# TCA785-W.net
KiCad netlist of a schematic drawn in Altium Designer
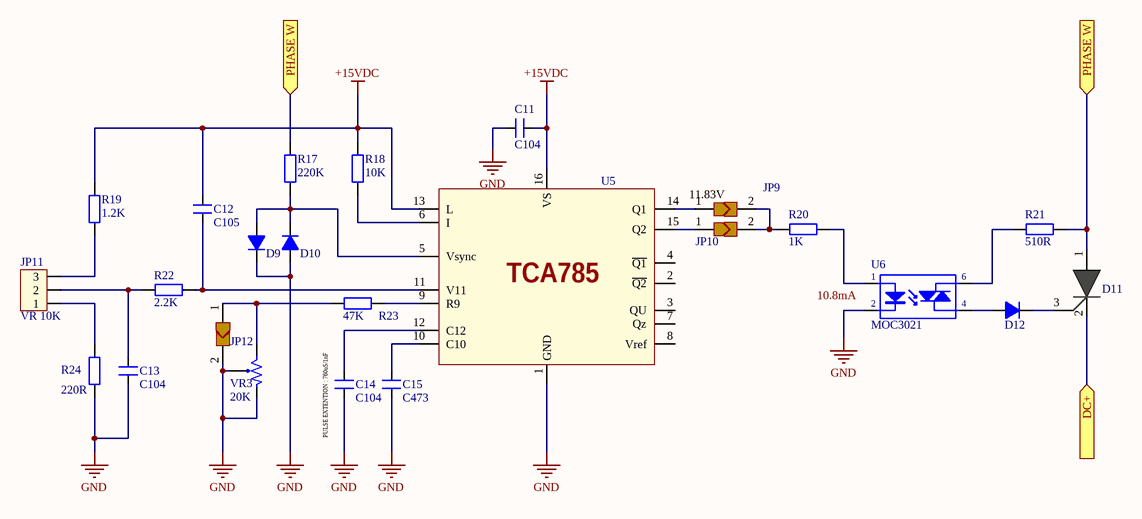
[diagram p0: TCA785-W.SchDoc]

(export (version "E")
  (design (tool "Eeschema 10.0.6"))
  (components
    (comp (ref "C11")
      (value "C104")
      (footprint "CN2-O")
      (description "CAP-gom")
      (libsource (lib "Sang_Library") (part "CAP-gom"))
    )
    (comp (ref "C12")
      (value "C105")
      (footprint "CN2-O")
      (description "CAP-gom")
      (libsource (lib "Sang_Library") (part "CAP-gom"))
    )
    (comp (ref "C13")
      (value "C104")
      (footprint "CN2-O")
      (description "CAP-gom")
      (libsource (lib "Sang_Library") (part "CAP-gom"))
    )
    (comp (ref "C14")
      (value "C104")
      (footprint "CN2-O")
      (description "CAP-gom")
      (libsource (lib "Sang_Library") (part "CAP-gom"))
    )
    (comp (ref "C15")
      (value "C473")
      (footprint "CN2-O")
      (description "CAP-gom")
      (libsource (lib "Sang_Library") (part "CAP-gom"))
    )
    (comp (ref "D9")
      (value "Diode  1N4007")
      (footprint "DO41-1A")
      (description "Diode 1A")
      (libsource (lib "Sang_Library") (part "Diode  1N4007"))
    )
    (comp (ref "D10")
      (value "Diode  1N4007")
      (footprint "DO41-1A")
      (description "Diode 1A")
      (libsource (lib "Sang_Library") (part "Diode  1N4007"))
    )
    (comp (ref "D11") (value "SCR") (footprint "TO-220") (libsource (lib "Huan") (part "BT151")))
    (comp (ref "D12")
      (value "Diode  1N4007")
      (footprint "DO41-1A")
      (description "Diode 1A")
      (libsource (lib "Sang_Library") (part "Diode  1N4007"))
    )
    (comp (ref "JP9")
      (value "PAD_Sellect")
      (footprint "PAD Select")
      (libsource (lib "Huan") (part "PAD_Sellect"))
    )
    (comp (ref "JP10")
      (value "PAD_Sellect")
      (footprint "PAD Select")
      (libsource (lib "Huan") (part "PAD_Sellect"))
    )
    (comp (ref "JP11")
      (value "VR 10K")
      (footprint "CON3")
      (description "Connector 3")
      (libsource (lib "syhaunguyen") (part "Con3"))
    )
    (comp (ref "JP12")
      (value "PAD_Sellect")
      (footprint "PAD Select")
      (libsource (lib "Huan") (part "PAD_Sellect"))
    )
    (comp (ref "R17")
      (value "220K")
      (footprint "R1/4W")
      (description "Resistor 1/4W")
      (libsource (lib "Sang_Library") (part "R1/4W"))
    )
    (comp (ref "R18")
      (value "10K")
      (footprint "R1/4W")
      (description "Resistor 1/4W")
      (libsource (lib "Sang_Library") (part "R1/4W"))
    )
    (comp (ref "R19")
      (value "1.2K")
      (footprint "R1/4W")
      (description "Resistor 1/4W")
      (libsource (lib "Sang_Library") (part "R1/4W"))
    )
    (comp (ref "R20")
      (value "1K")
      (footprint "R1/4W")
      (description "Resistor 1/4W")
      (libsource (lib "Sang_Library") (part "R1/4W"))
    )
    (comp (ref "R21")
      (value "510R")
      (footprint "R1/4W")
      (description "Resistor 1/4W")
      (libsource (lib "Sang_Library") (part "R1/4W"))
    )
    (comp (ref "R22")
      (value "2.2K")
      (footprint "R1/4W")
      (description "Resistor 1/4W")
      (libsource (lib "Sang_Library") (part "R1/4W"))
    )
    (comp (ref "R23")
      (value "47K")
      (footprint "R1/4W")
      (description "Resistor 1/4W")
      (libsource (lib "Sang_Library") (part "R1/4W"))
    )
    (comp (ref "R24")
      (value "220R")
      (footprint "R1/4W")
      (description "Resistor 1/4W")
      (libsource (lib "Sang_Library") (part "R1/4W"))
    )
    (comp (ref "U5") (value "TCA785Q") (footprint "DIP-16") (libsource (lib "Huan") (part "TCA785Q")))
    (comp (ref "U6")
      (value "MOC3021")
      (footprint "DIP6/W0.3 - MOC3021")
      (description "Single Opto")
      (libsource (lib "Sang_Library") (part "MOC3021"))
    )
    (comp (ref "VR3")
      (value "20K")
      (footprint "VR")
      (description "Var Resistor RM065")
      (libsource (lib "Sang_Library") (part "VR"))
    )
  )
  (nets
    (net (code "1") (name "+15VDC") (class "Default")
      (node (ref "C11") (pin "2") (pinfunction "2_2") (pintype "passive"))
      (node (ref "C12") (pin "2") (pinfunction "2_2") (pintype "passive"))
      (node (ref "R18") (pin "1") (pinfunction "1_1") (pintype "passive"))
      (node (ref "R19") (pin "2") (pinfunction "2_2") (pintype "passive"))
      (node (ref "U5") (pin "13") (pinfunction "L_13") (pintype "passive"))
      (node (ref "U5") (pin "16") (pinfunction "VS_16") (pintype "passive"))
    )
    (net (code "3") (name "/DC+") (class "Default")
      (node (ref "D11") (pin "2") (pinfunction "K_2") (pintype "passive"))
    )
    (net (code "4") (name "/PHASE W") (class "Default")
      (node (ref "D11") (pin "1") (pinfunction "A_1") (pintype "passive"))
      (node (ref "R17") (pin "1") (pinfunction "1_1") (pintype "passive"))
      (node (ref "R21") (pin "1") (pinfunction "1_1") (pintype "passive"))
    )
    (net (code "5") (name "GND") (class "Default")
      (node (ref "C11") (pin "1") (pinfunction "1_1") (pintype "passive"))
      (node (ref "C13") (pin "1") (pinfunction "1_1") (pintype "passive"))
      (node (ref "C14") (pin "1") (pinfunction "1_1") (pintype "passive"))
      (node (ref "C15") (pin "1") (pinfunction "1_1") (pintype "passive"))
      (node (ref "D10") (pin "1") (pinfunction "1_1") (pintype "passive"))
      (node (ref "D9") (pin "2") (pinfunction "2_2") (pintype "passive"))
      (node (ref "JP12") (pin "2") (pinfunction "2_2") (pintype "passive"))
      (node (ref "R24") (pin "1") (pinfunction "1_1") (pintype "passive"))
      (node (ref "U5") (pin "1") (pinfunction "GND_1") (pintype "passive"))
      (node (ref "U6") (pin "2") (pinfunction "K_2") (pintype "passive"))
      (node (ref "VR3") (pin "1") (pinfunction "1_1") (pintype "passive"))
      (node (ref "VR3") (pin "2") (pinfunction "2_2") (pintype "passive"))
    )
    (net (code "6") (name "Net-(C13-Pad2)") (class "Default")
      (node (ref "C13") (pin "2") (pinfunction "2_2") (pintype "passive"))
      (node (ref "JP11") (pin "2") (pinfunction "2_2") (pintype "passive"))
      (node (ref "R22") (pin "2") (pinfunction "2_2") (pintype "passive"))
    )
    (net (code "7") (name "Net-(D11-G)") (class "Default")
      (node (ref "D11") (pin "3") (pinfunction "G_3") (pintype "passive"))
      (node (ref "D12") (pin "2") (pinfunction "2_2") (pintype "passive"))
    )
    (net (code "8") (name "Net-(JP10-Pad2)") (class "Default")
      (node (ref "JP10") (pin "2") (pinfunction "2_2") (pintype "passive"))
      (node (ref "JP9") (pin "2") (pinfunction "2_2") (pintype "passive"))
      (node (ref "R20") (pin "2") (pinfunction "2_2") (pintype "passive"))
    )
    (net (code "9") (name "Net-(JP11-Pad1)") (class "Default")
      (node (ref "JP11") (pin "1") (pinfunction "1_1") (pintype "passive"))
      (node (ref "R24") (pin "2") (pinfunction "2_2") (pintype "passive"))
    )
    (net (code "10") (name "Net-(JP11-Pad3)") (class "Default")
      (node (ref "JP11") (pin "3") (pinfunction "3_3") (pintype "passive"))
      (node (ref "R19") (pin "1") (pinfunction "1_1") (pintype "passive"))
    )
    (net (code "11") (name "Net-(JP12-Pad1)") (class "Default")
      (node (ref "JP12") (pin "1") (pinfunction "1_1") (pintype "passive"))
      (node (ref "R23") (pin "1") (pinfunction "1_1") (pintype "passive"))
      (node (ref "VR3") (pin "3") (pinfunction "3_3") (pintype "passive"))
    )
    (net (code "12") (name "Net-(U5-C10)") (class "Default")
      (node (ref "C15") (pin "2") (pinfunction "2_2") (pintype "passive"))
      (node (ref "U5") (pin "10") (pinfunction "C10_10") (pintype "passive"))
    )
    (net (code "13") (name "Net-(U5-C12)") (class "Default")
      (node (ref "C14") (pin "2") (pinfunction "2_2") (pintype "passive"))
      (node (ref "U5") (pin "12") (pinfunction "C12_12") (pintype "passive"))
    )
    (net (code "14") (name "Net-(U5-I)") (class "Default")
      (node (ref "R18") (pin "2") (pinfunction "2_2") (pintype "passive"))
      (node (ref "U5") (pin "6") (pinfunction "I_6") (pintype "passive"))
    )
    (net (code "15") (name "Net-(U5-Q1)") (class "Default")
      (node (ref "JP9") (pin "1") (pinfunction "1_1") (pintype "passive"))
      (node (ref "U5") (pin "14") (pinfunction "Q1_14") (pintype "passive"))
    )
    (net (code "16") (name "Net-(U5-Q2)") (class "Default")
      (node (ref "JP10") (pin "1") (pinfunction "1_1") (pintype "passive"))
      (node (ref "U5") (pin "15") (pinfunction "Q2_15") (pintype "passive"))
    )
    (net (code "17") (name "Net-(U5-R9)") (class "Default")
      (node (ref "R23") (pin "2") (pinfunction "2_2") (pintype "passive"))
      (node (ref "U5") (pin "9") (pinfunction "R9_9") (pintype "passive"))
    )
    (net (code "18") (name "Net-(U5-V11)") (class "Default")
      (node (ref "C12") (pin "1") (pinfunction "1_1") (pintype "passive"))
      (node (ref "R22") (pin "1") (pinfunction "1_1") (pintype "passive"))
      (node (ref "U5") (pin "11") (pinfunction "V11_11") (pintype "passive"))
    )
    (net (code "19") (name "Net-(U5-Vsync)") (class "Default")
      (node (ref "D10") (pin "2") (pinfunction "2_2") (pintype "passive"))
      (node (ref "D9") (pin "1") (pinfunction "1_1") (pintype "passive"))
      (node (ref "R17") (pin "2") (pinfunction "2_2") (pintype "passive"))
      (node (ref "U5") (pin "5") (pinfunction "Vsync_5") (pintype "passive"))
    )
    (net (code "20") (name "Net-(U6-A)") (class "Default")
      (node (ref "R20") (pin "1") (pinfunction "1_1") (pintype "passive"))
      (node (ref "U6") (pin "1") (pinfunction "A_1") (pintype "passive"))
    )
    (net (code "21") (name "Net-(U6-C)") (class "Default")
      (node (ref "R21") (pin "2") (pinfunction "2_2") (pintype "passive"))
      (node (ref "U6") (pin "6") (pinfunction "C_6") (pintype "passive"))
    )
    (net (code "22") (name "Net-(U6-E)") (class "Default")
      (node (ref "D12") (pin "1") (pinfunction "1_1") (pintype "passive"))
      (node (ref "U6") (pin "4") (pinfunction "E_4") (pintype "passive"))
    )
    (net (code "23") (name "unconnected-(U5-QU-Pad3)") (class "Default")
      (node (ref "U5") (pin "3") (pinfunction "QU_3") (pintype "passive"))
    )
    (net (code "24") (name "unconnected-(U5-Qz-Pad7)") (class "Default")
      (node (ref "U5") (pin "7") (pinfunction "Qz_7") (pintype "passive"))
    )
    (net (code "25") (name "unconnected-(U5-Vref-Pad8)") (class "Default")
      (node (ref "U5") (pin "8") (pinfunction "Vref_8") (pintype "passive"))
    )
    (net (code "26") (name "unconnected-(U5-~{Q1}-Pad4)") (class "Default")
      (node (ref "U5") (pin "4") (pinfunction "~{Q1}_4") (pintype "passive"))
    )
    (net (code "27") (name "unconnected-(U5-~{Q2}-Pad2)") (class "Default")
      (node (ref "U5") (pin "2") (pinfunction "~{Q2}_2") (pintype "passive"))
    )
  )
)
